# CC_EXP.net
KiCad netlist of a schematic drawn in Altium Designer
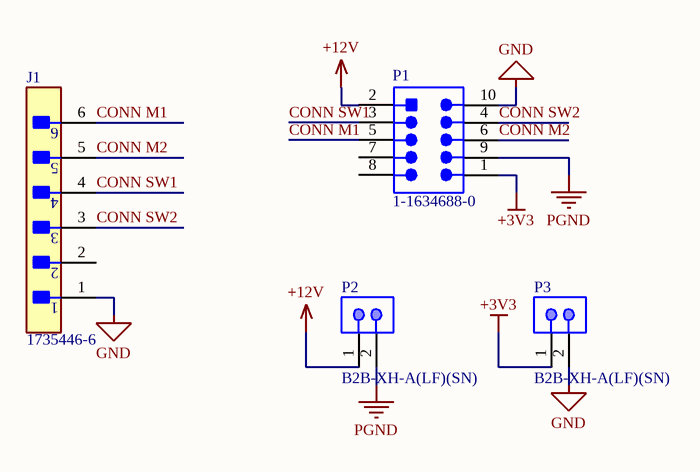
[diagram p0: CC_EXP.SchDoc]

(export (version "E")
  (design (tool "Eeschema 10.0.6"))
  (components
    (comp (ref "J1")
      (value "1735446-6")
      (footprint "FP-1735446-6-MFG")
      (description "CONN HEADER VERT 6POS 2MM")
      (fields
        (field (name "MANUFACTURER") "TE")
        (field (name "OCTOPART") "https://octopart.com/1735446-6-te+connectivity-42205942")
      )
      (libsource (lib "Altium Content Vault") (part "f2cb566baf1c37ab5a3b8e90bbeafd6"))
    )
    (comp (ref "P1")
      (value "1-1634688-0")
      (footprint "TECO-1-1634688-0-10_V")
      (fields (field (name "MANUFACTURER") "TE Connectivity"))
      (libsource (lib "Altium Content Vault") (part "CN-2P-M-R10"))
    )
    (comp (ref "P2")
      (value "B2B-XH-A(LF)(SN)")
      (footprint "JST-B2B-XH-A_V")
      (fields (field (name "MANUFACTURER") "JST"))
      (libsource (lib "Altium Content Vault") (part "CN-1P-M-R2"))
    )
    (comp (ref "P3")
      (value "B2B-XH-A(LF)(SN)")
      (footprint "JST-B2B-XH-A_V")
      (fields (field (name "MANUFACTURER") "JST"))
      (libsource (lib "Altium Content Vault") (part "CN-1P-M-R2"))
    )
  )
  (nets
    (net (code "1") (name "+3V3") (class "Default")
      (node (ref "P1") (pin "1") (pinfunction "1_1") (pintype "passive"))
      (node (ref "P3") (pin "1") (pinfunction "1_1") (pintype "passive"))
    )
    (net (code "2") (name "+12V") (class "Default")
      (node (ref "P1") (pin "2") (pinfunction "2_2") (pintype "passive"))
      (node (ref "P2") (pin "1") (pinfunction "1_1") (pintype "passive"))
    )
    (net (code "3") (name "/CONN M1") (class "Default")
      (node (ref "J1") (pin "6") (pinfunction "6_6") (pintype "passive"))
      (node (ref "P1") (pin "5") (pinfunction "5_5") (pintype "passive"))
    )
    (net (code "4") (name "/CONN M2") (class "Default")
      (node (ref "J1") (pin "5") (pinfunction "5_5") (pintype "passive"))
      (node (ref "P1") (pin "6") (pinfunction "6_6") (pintype "passive"))
    )
    (net (code "5") (name "/CONN SW1") (class "Default")
      (node (ref "J1") (pin "4") (pinfunction "4_4") (pintype "passive"))
      (node (ref "P1") (pin "3") (pinfunction "3_3") (pintype "passive"))
    )
    (net (code "6") (name "/CONN SW2") (class "Default")
      (node (ref "J1") (pin "3") (pinfunction "3_3") (pintype "passive"))
      (node (ref "P1") (pin "4") (pinfunction "4_4") (pintype "passive"))
    )
    (net (code "7") (name "GND") (class "Default")
      (node (ref "J1") (pin "1") (pinfunction "1_1") (pintype "passive"))
      (node (ref "P1") (pin "10") (pinfunction "10_10") (pintype "passive"))
      (node (ref "P3") (pin "2") (pinfunction "2_2") (pintype "passive"))
    )
    (net (code "8") (name "PGND") (class "Default")
      (node (ref "P1") (pin "9") (pinfunction "9_9") (pintype "passive"))
      (node (ref "P2") (pin "2") (pinfunction "2_2") (pintype "passive"))
    )
    (net (code "9") (name "unconnected-(J1-Pad2)") (class "Default")
      (node (ref "J1") (pin "2") (pinfunction "2_2") (pintype "passive"))
    )
    (net (code "10") (name "unconnected-(P1-Pad7)") (class "Default")
      (node (ref "P1") (pin "7") (pinfunction "7_7") (pintype "passive"))
    )
    (net (code "11") (name "unconnected-(P1-Pad8)") (class "Default")
      (node (ref "P1") (pin "8") (pinfunction "8_8") (pintype "passive"))
    )
  )
)
